# Keg_Cop_-_Tallboy.net
KiCad netlist of a schematic drawn in EAGLE
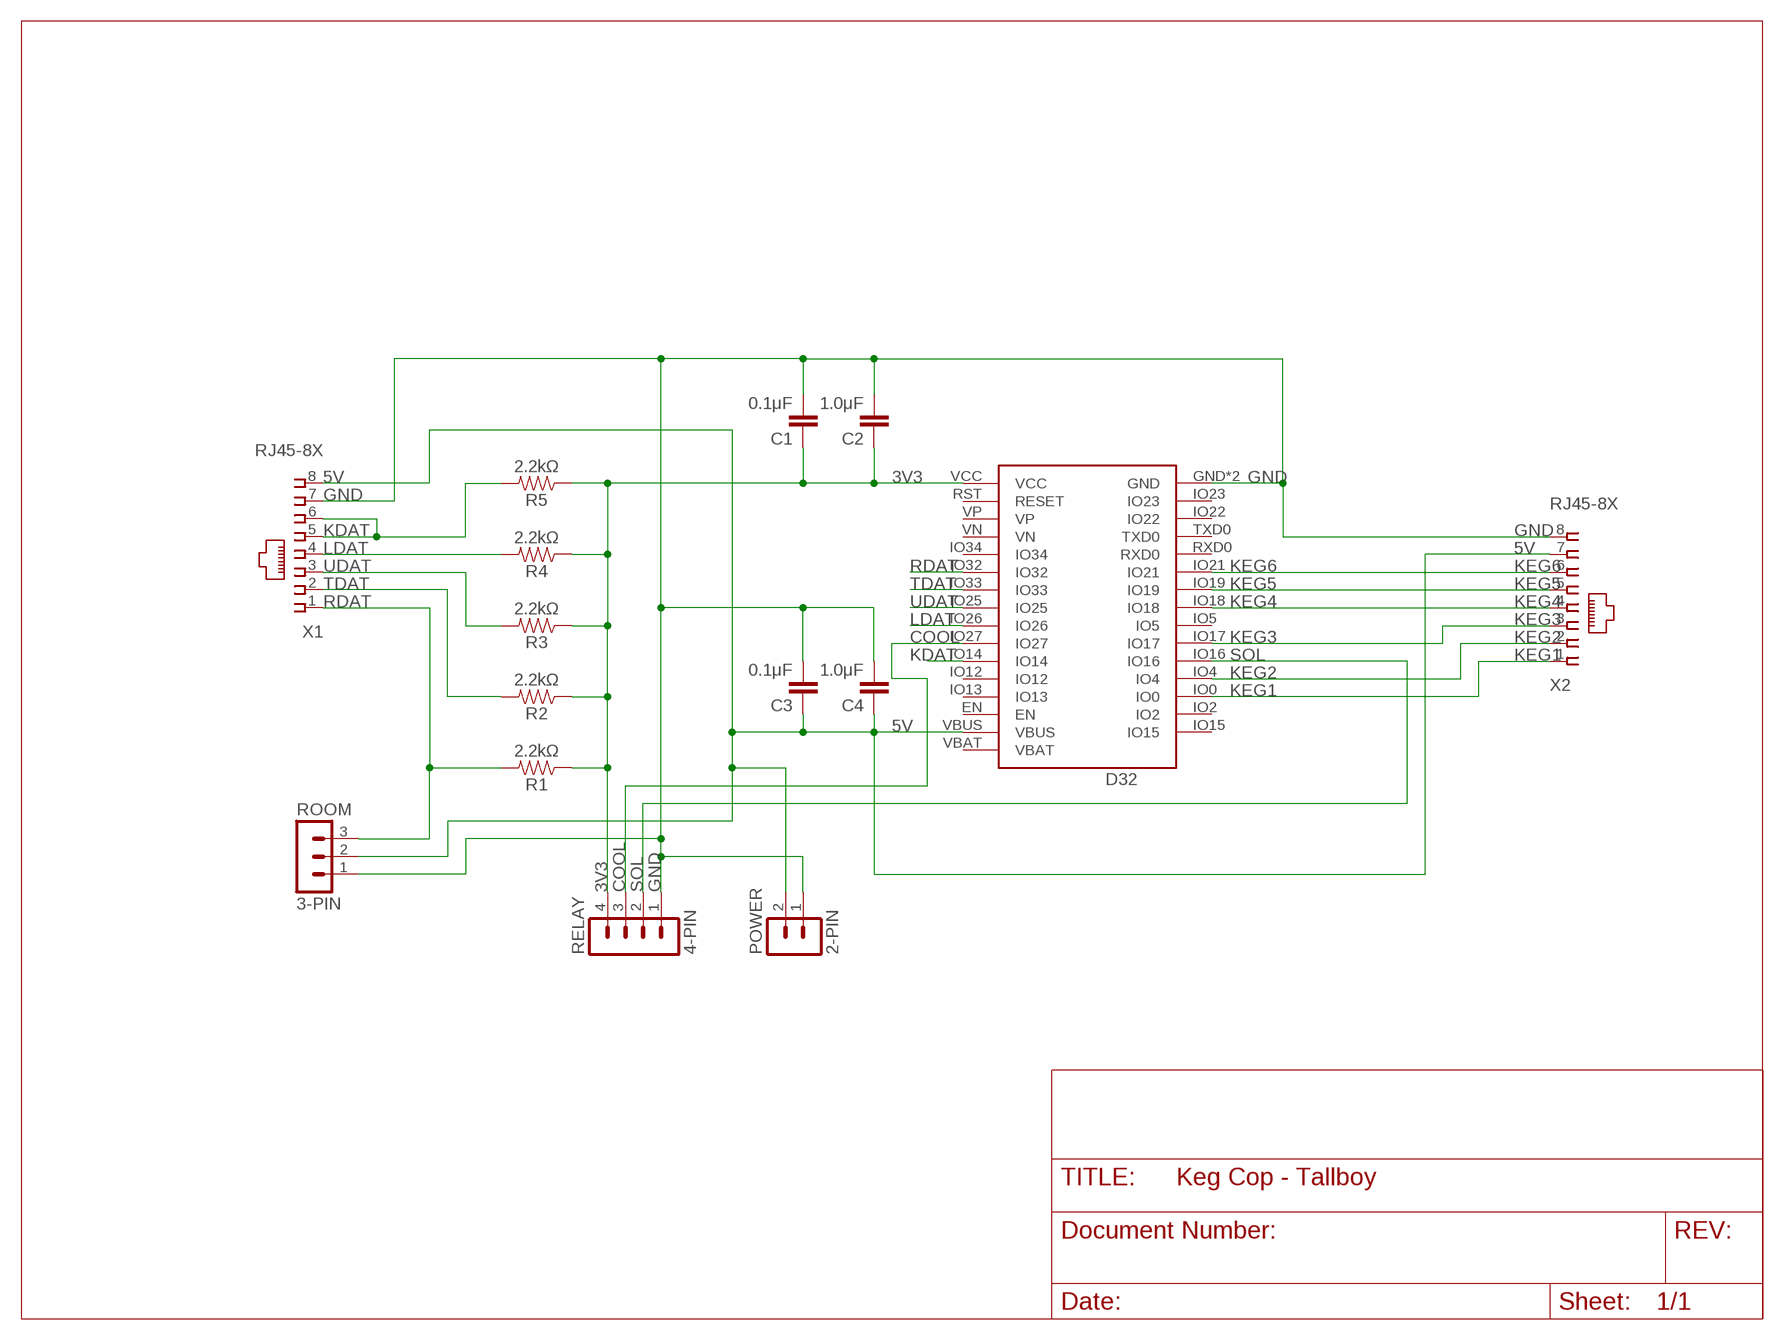
[diagram p0: schematic, sheet 1]

(export (version "E")
  (design (tool "Eeschema 10.0.6"))
  (components
    (comp (ref "C1")
      (value "0.1μF")
      (footprint "eagle-import:CAP_PTH-2.54")
      (libsource (lib "eagle-import") (part "CAP_CERAMIC_2.54"))
    )
    (comp (ref "C2")
      (value "1.0μF")
      (footprint "eagle-import:CAP_PTH-2.54")
      (libsource (lib "eagle-import") (part "CAP_CERAMIC_2.54"))
    )
    (comp (ref "C3")
      (value "0.1μF")
      (footprint "eagle-import:CAP_PTH-2.54")
      (libsource (lib "eagle-import") (part "CAP_CERAMIC_2.54"))
    )
    (comp (ref "C4")
      (value "1.0μF")
      (footprint "eagle-import:CAP_PTH-2.54")
      (libsource (lib "eagle-import") (part "CAP_CERAMIC_2.54"))
    )
    (comp (ref "D32")
      (value "Lolin D32")
      (footprint "eagle-import:D32_NO_BATT")
      (libsource (lib "eagle-import") (part "WEMOS-D32D32_NO_BATT"))
    )
    (comp (ref "POWER")
      (value "2-PIN")
      (footprint "eagle-import:HDR-2_VERT")
      (libsource (lib "eagle-import") (part "HDR-2"))
    )
    (comp (ref "R1")
      (value "2.2kΩ")
      (footprint "eagle-import:AXIAL-0.3")
      (libsource (lib "eagle-import") (part "RESISTORAXIAL-0.3"))
    )
    (comp (ref "R2")
      (value "2.2kΩ")
      (footprint "eagle-import:AXIAL-0.3")
      (libsource (lib "eagle-import") (part "RESISTORAXIAL-0.3"))
    )
    (comp (ref "R3")
      (value "2.2kΩ")
      (footprint "eagle-import:AXIAL-0.3")
      (libsource (lib "eagle-import") (part "RESISTORAXIAL-0.3"))
    )
    (comp (ref "R4")
      (value "2.2kΩ")
      (footprint "eagle-import:AXIAL-0.3")
      (libsource (lib "eagle-import") (part "RESISTORAXIAL-0.3"))
    )
    (comp (ref "R5")
      (value "2.2kΩ")
      (footprint "eagle-import:AXIAL-0.3")
      (libsource (lib "eagle-import") (part "RESISTORAXIAL-0.3"))
    )
    (comp (ref "RELAY")
      (value "4-PIN")
      (footprint "eagle-import:MA04-1")
      (libsource (lib "eagle-import") (part "MA04-1"))
    )
    (comp (ref "ROOM")
      (value "3-PIN")
      (footprint "eagle-import:HDR-3_VERT")
      (libsource (lib "eagle-import") (part "HDR-3"))
    )
    (comp (ref "X1")
      (value "RJ45-8X")
      (footprint "eagle-import:RJ45-NO-SHIELD")
      (libsource (lib "eagle-import") (part "RJ45-8X"))
    )
    (comp (ref "X2")
      (value "RJ45-8X")
      (footprint "eagle-import:RJ45-NO-SHIELD")
      (libsource (lib "eagle-import") (part "RJ45-8X"))
    )
  )
  (nets
    (net (code "1") (name "/3V3") (class "Default")
      (node (ref "C1") (pin "1") (pinfunction "1_1") (pintype "passive"))
      (node (ref "C2") (pin "1") (pinfunction "1_1") (pintype "passive"))
      (node (ref "D32") (pin "VCC") (pinfunction "VCC_VCC") (pintype "power_in"))
      (node (ref "R1") (pin "P$1") (pinfunction "1_P$1") (pintype "passive"))
      (node (ref "R2") (pin "P$1") (pinfunction "1_P$1") (pintype "passive"))
      (node (ref "R3") (pin "P$1") (pinfunction "1_P$1") (pintype "passive"))
      (node (ref "R4") (pin "P$1") (pinfunction "1_P$1") (pintype "passive"))
      (node (ref "R5") (pin "P$1") (pinfunction "1_P$1") (pintype "passive"))
      (node (ref "RELAY") (pin "4") (pinfunction "4_4") (pintype "passive"))
    )
    (net (code "2") (name "/5V") (class "Default")
      (node (ref "C3") (pin "1") (pinfunction "1_1") (pintype "passive"))
      (node (ref "C4") (pin "1") (pinfunction "1_1") (pintype "passive"))
      (node (ref "D32") (pin "VBUS") (pinfunction "VBUS_VBUS") (pintype "bidirectional"))
      (node (ref "POWER") (pin "2") (pinfunction "2_2") (pintype "passive"))
      (node (ref "ROOM") (pin "2") (pinfunction "2_2") (pintype "passive"))
      (node (ref "X1") (pin "8") (pinfunction "8_8") (pintype "passive"))
      (node (ref "X2") (pin "7") (pinfunction "7_7") (pintype "passive"))
    )
    (net (code "3") (name "/COOL") (class "Default")
      (node (ref "D32") (pin "IO27") (pinfunction "IO27_IO27") (pintype "bidirectional"))
      (node (ref "RELAY") (pin "3") (pinfunction "3_3") (pintype "passive"))
    )
    (net (code "4") (name "/GND") (class "Default")
      (node (ref "C1") (pin "2") (pinfunction "2_2") (pintype "passive"))
      (node (ref "C2") (pin "2") (pinfunction "2_2") (pintype "passive"))
      (node (ref "C3") (pin "2") (pinfunction "2_2") (pintype "passive"))
      (node (ref "C4") (pin "2") (pinfunction "2_2") (pintype "passive"))
      (node (ref "D32") (pin "GND") (pinfunction "GND_GND") (pintype "power_in"))
      (node (ref "D32") (pin "GND2") (pinfunction "GND_GND2") (pintype "power_in"))
      (node (ref "POWER") (pin "1") (pinfunction "1_1") (pintype "passive"))
      (node (ref "RELAY") (pin "1") (pinfunction "1_1") (pintype "passive"))
      (node (ref "ROOM") (pin "1") (pinfunction "1_1") (pintype "passive"))
      (node (ref "X1") (pin "7") (pinfunction "7_7") (pintype "passive"))
      (node (ref "X2") (pin "8") (pinfunction "8_8") (pintype "passive"))
    )
    (net (code "5") (name "/KDAT") (class "Default")
      (node (ref "D32") (pin "IO14") (pinfunction "IO14_IO14") (pintype "bidirectional"))
      (node (ref "R5") (pin "P$2") (pinfunction "2_P$2") (pintype "passive"))
      (node (ref "X1") (pin "5") (pinfunction "5_5") (pintype "passive"))
      (node (ref "X1") (pin "6") (pinfunction "6_6") (pintype "passive"))
    )
    (net (code "6") (name "/KEG1") (class "Default")
      (node (ref "D32") (pin "IO0") (pinfunction "IO0_IO0") (pintype "bidirectional"))
      (node (ref "X2") (pin "1") (pinfunction "1_1") (pintype "passive"))
    )
    (net (code "7") (name "/KEG2") (class "Default")
      (node (ref "D32") (pin "IO4") (pinfunction "IO4_IO4") (pintype "bidirectional"))
      (node (ref "X2") (pin "2") (pinfunction "2_2") (pintype "passive"))
    )
    (net (code "8") (name "/KEG3") (class "Default")
      (node (ref "D32") (pin "IO17") (pinfunction "IO17_IO17") (pintype "bidirectional"))
      (node (ref "X2") (pin "3") (pinfunction "3_3") (pintype "passive"))
    )
    (net (code "9") (name "/KEG4") (class "Default")
      (node (ref "D32") (pin "IO18") (pinfunction "IO18_IO18") (pintype "bidirectional"))
      (node (ref "X2") (pin "4") (pinfunction "4_4") (pintype "passive"))
    )
    (net (code "10") (name "/KEG5") (class "Default")
      (node (ref "D32") (pin "IO19") (pinfunction "IO19_IO19") (pintype "bidirectional"))
      (node (ref "X2") (pin "5") (pinfunction "5_5") (pintype "passive"))
    )
    (net (code "11") (name "/KEG6") (class "Default")
      (node (ref "D32") (pin "IO21") (pinfunction "IO21_IO21") (pintype "bidirectional"))
      (node (ref "X2") (pin "6") (pinfunction "6_6") (pintype "passive"))
    )
    (net (code "12") (name "/LDAT") (class "Default")
      (node (ref "D32") (pin "IO26") (pinfunction "IO26_IO26") (pintype "bidirectional"))
      (node (ref "R4") (pin "P$2") (pinfunction "2_P$2") (pintype "passive"))
      (node (ref "X1") (pin "4") (pinfunction "4_4") (pintype "passive"))
    )
    (net (code "13") (name "/RDAT") (class "Default")
      (node (ref "D32") (pin "IO32") (pinfunction "IO32_IO32") (pintype "bidirectional"))
      (node (ref "R1") (pin "P$2") (pinfunction "2_P$2") (pintype "passive"))
      (node (ref "ROOM") (pin "3") (pinfunction "3_3") (pintype "passive"))
      (node (ref "X1") (pin "1") (pinfunction "1_1") (pintype "passive"))
    )
    (net (code "14") (name "/SOL") (class "Default")
      (node (ref "D32") (pin "IO16") (pinfunction "IO16_IO16") (pintype "bidirectional"))
      (node (ref "RELAY") (pin "2") (pinfunction "2_2") (pintype "passive"))
    )
    (net (code "15") (name "/TDAT") (class "Default")
      (node (ref "D32") (pin "IO33") (pinfunction "IO33_IO33") (pintype "bidirectional"))
      (node (ref "R2") (pin "P$2") (pinfunction "2_P$2") (pintype "passive"))
      (node (ref "X1") (pin "2") (pinfunction "2_2") (pintype "passive"))
    )
    (net (code "16") (name "/UDAT") (class "Default")
      (node (ref "D32") (pin "IO25") (pinfunction "IO25_IO25") (pintype "bidirectional"))
      (node (ref "R3") (pin "P$2") (pinfunction "2_P$2") (pintype "passive"))
      (node (ref "X1") (pin "3") (pinfunction "3_3") (pintype "passive"))
    )
    (net (code "17") (name "unconnected-(D32-PadEN)") (class "Default")
      (node (ref "D32") (pin "EN") (pinfunction "EN_EN") (pintype "bidirectional"))
    )
    (net (code "18") (name "unconnected-(D32-PadIO2)") (class "Default")
      (node (ref "D32") (pin "IO2") (pinfunction "IO2_IO2") (pintype "bidirectional"))
    )
    (net (code "19") (name "unconnected-(D32-PadIO5)") (class "Default")
      (node (ref "D32") (pin "IO5") (pinfunction "IO5_IO5") (pintype "bidirectional"))
    )
    (net (code "20") (name "unconnected-(D32-PadIO12)") (class "Default")
      (node (ref "D32") (pin "IO12") (pinfunction "IO12_IO12") (pintype "bidirectional"))
    )
    (net (code "21") (name "unconnected-(D32-PadIO13)") (class "Default")
      (node (ref "D32") (pin "IO13") (pinfunction "IO13_IO13") (pintype "bidirectional"))
    )
    (net (code "22") (name "unconnected-(D32-PadIO15)") (class "Default")
      (node (ref "D32") (pin "IO15") (pinfunction "IO15_IO15") (pintype "bidirectional"))
    )
    (net (code "23") (name "unconnected-(D32-PadIO22)") (class "Default")
      (node (ref "D32") (pin "IO22") (pinfunction "IO22_IO22") (pintype "bidirectional"))
    )
    (net (code "24") (name "unconnected-(D32-PadIO23)") (class "Default")
      (node (ref "D32") (pin "IO23") (pinfunction "IO23_IO23") (pintype "bidirectional"))
    )
    (net (code "25") (name "unconnected-(D32-PadIO34)") (class "Default")
      (node (ref "D32") (pin "IO34") (pinfunction "IO34_IO34") (pintype "bidirectional"))
    )
    (net (code "26") (name "unconnected-(D32-PadRXD0)") (class "Default")
      (node (ref "D32") (pin "RXD0") (pinfunction "RXD0_RXD0") (pintype "input"))
    )
    (net (code "27") (name "unconnected-(D32-PadTXD0)") (class "Default")
      (node (ref "D32") (pin "TXD0") (pinfunction "TXD0_TXD0") (pintype "output"))
    )
    (net (code "28") (name "unconnected-(D32-PadVBAT)") (class "Default")
      (node (ref "D32") (pin "VBAT") (pinfunction "VBAT_VBAT") (pintype "bidirectional"))
    )
    (net (code "29") (name "unconnected-(D32-PadVN)") (class "Default")
      (node (ref "D32") (pin "VN") (pinfunction "VN_VN") (pintype "bidirectional"))
    )
    (net (code "30") (name "unconnected-(D32-PadVP)") (class "Default")
      (node (ref "D32") (pin "VP") (pinfunction "VP_VP") (pintype "bidirectional"))
    )
    (net (code "31") (name "unconnected-(D32-RESET-PadRST)") (class "Default")
      (node (ref "D32") (pin "RST") (pinfunction "RESET_RST") (pintype "bidirectional"))
    )
  )
)
